# Sensors.net
KiCad netlist of a schematic drawn in Altium Designer
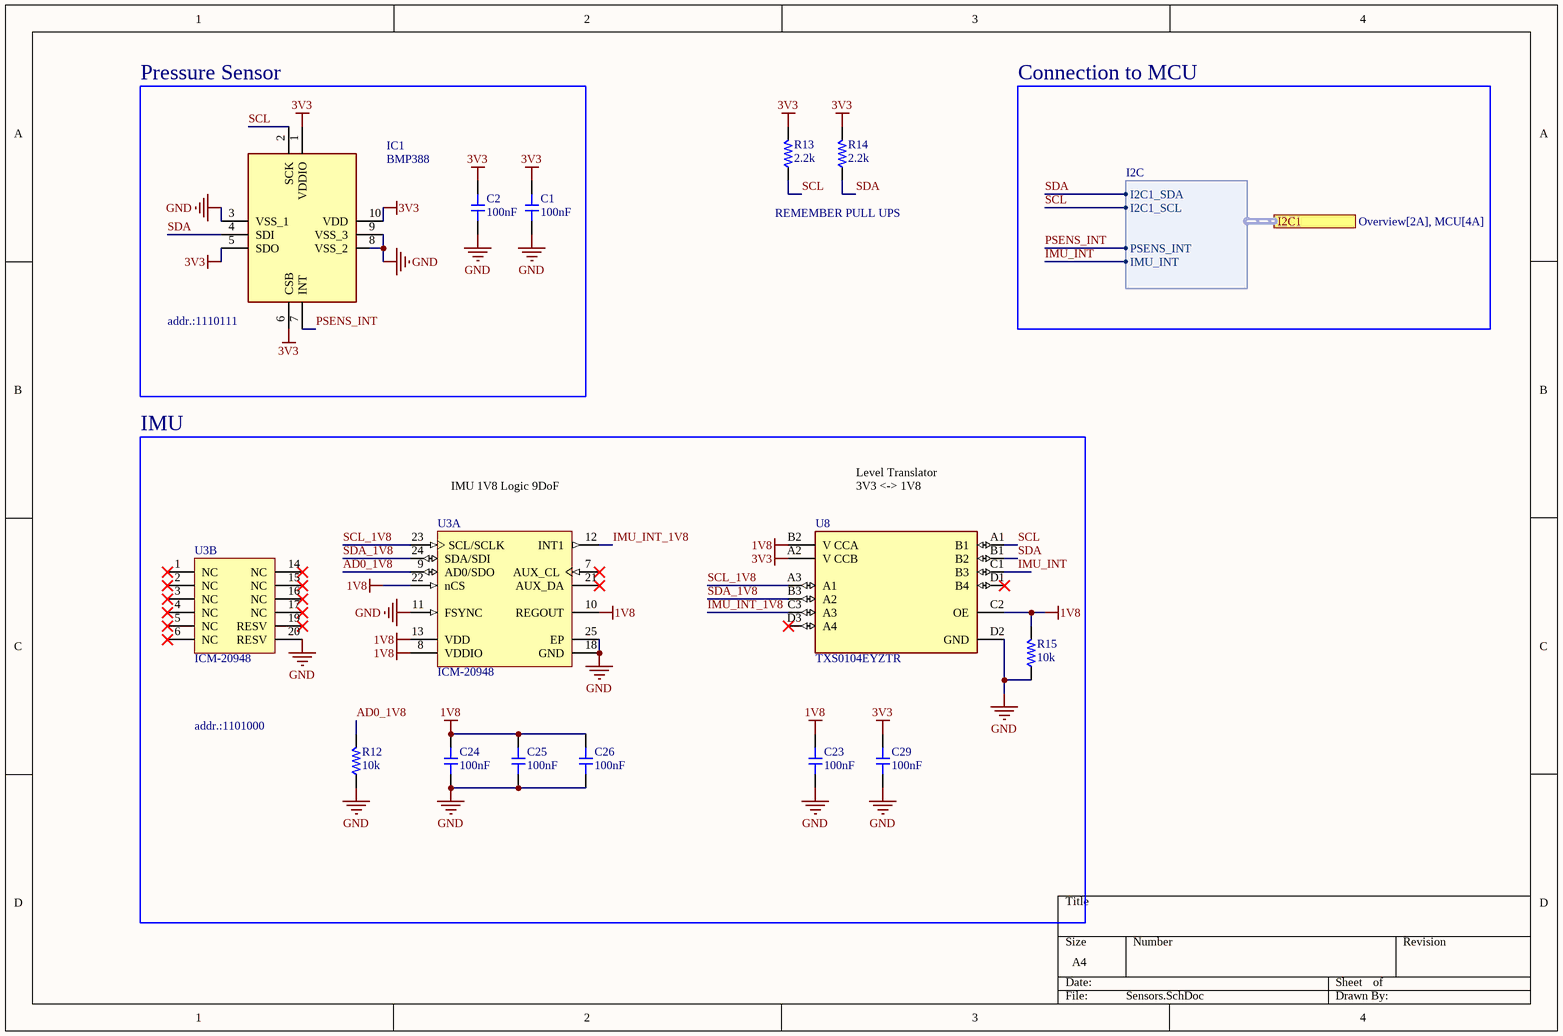
[diagram p0: Sensors.SchDoc]

(export (version "E")
  (design (tool "Eeschema 10.0.6"))
  (components
    (comp (ref "C1")
      (value "100nF")
      (footprint "CAP-0402")
      (description "Capacitor, Ceramic (MLCC), 100nF, ±10%, 16V, X7R, ±10%, SMD 0402")
      (fields (field (name "TOLERANCE") "10%") (field (name "JLCPCB BASIC PART") "Yes"))
      (libsource (lib "StrathSEDS") (part "GRM21BR61H106KE43L"))
    )
    (comp (ref "C2")
      (value "100nF")
      (footprint "CAP-0402")
      (description "Capacitor, Ceramic (MLCC), 100nF, ±10%, 16V, X7R, ±10%, SMD 0402")
      (fields (field (name "TOLERANCE") "10%") (field (name "JLCPCB BASIC PART") "Yes"))
      (libsource (lib "StrathSEDS") (part "GRM21BR61H106KE43L"))
    )
    (comp (ref "C23")
      (value "100nF")
      (footprint "CAP-0402")
      (description "Capacitor, Ceramic (MLCC), 100nF, ±10%, 16V, X7R, ±10%, SMD 0402")
      (fields (field (name "TOLERANCE") "10%") (field (name "JLCPCB BASIC PART") "Yes"))
      (libsource (lib "StrathSEDS") (part "GRM21BR61H106KE43L"))
    )
    (comp (ref "C24")
      (value "100nF")
      (footprint "CAP-0402")
      (description "Capacitor, Ceramic (MLCC), 100nF, ±10%, 16V, X7R, ±10%, SMD 0402")
      (fields (field (name "TOLERANCE") "10%") (field (name "JLCPCB BASIC PART") "Yes"))
      (libsource (lib "StrathSEDS") (part "GRM21BR61H106KE43L"))
    )
    (comp (ref "C25")
      (value "100nF")
      (footprint "CAP-0402")
      (description "Capacitor, Ceramic (MLCC), 100nF, ±10%, 16V, X7R, ±10%, SMD 0402")
      (fields (field (name "TOLERANCE") "10%") (field (name "JLCPCB BASIC PART") "Yes"))
      (libsource (lib "StrathSEDS") (part "GRM21BR61H106KE43L"))
    )
    (comp (ref "C26")
      (value "100nF")
      (footprint "CAP-0402")
      (description "Capacitor, Ceramic (MLCC), 100nF, ±10%, 16V, X7R, ±10%, SMD 0402")
      (fields (field (name "TOLERANCE") "10%") (field (name "JLCPCB BASIC PART") "Yes"))
      (libsource (lib "StrathSEDS") (part "GRM21BR61H106KE43L"))
    )
    (comp (ref "C29")
      (value "100nF")
      (footprint "CAP-0402")
      (description "Capacitor, Ceramic (MLCC), 100nF, ±10%, 16V, X7R, ±10%, SMD 0402")
      (fields (field (name "TOLERANCE") "10%") (field (name "JLCPCB BASIC PART") "Yes"))
      (libsource (lib "StrathSEDS") (part "GRM21BR61H106KE43L"))
    )
    (comp (ref "IC1")
      (value "BMP388")
      (footprint "BMP388")
      (description "Pressure Sensor 30kPa to 125kPa Absolute 10-Pin LGA")
      (fields (field (name "LCSC PART #") "C779278"))
      (libsource (lib "StrathSEDS") (part "BMP388"))
    )
    (comp (ref "R12")
      (value "10k")
      (footprint "RES-0402")
      (description "Resistor, 10kΩ, ±1%, 62.5mW, 50V, ±100ppm/℃, -55℃~+155℃, SMD 0402")
      (fields (field (name "TOLERANCE") "1%") (field (name "JLCPCB PART NUMBER") "C25744"))
      (libsource (lib "StrathSEDS") (part "1206W4F7500T5E"))
    )
    (comp (ref "R13")
      (value "2.2k")
      (footprint "RES-0402")
      (description "Resistor, 2.2kΩ, ±1%, 62.5mW, 50V, ±100ppm/℃, -55℃~+155℃, SMD 0402")
      (fields (field (name "JLCPCB BASIC PART") "Yes") (field (name "MANUFACTURER") "Uniroyal"))
      (libsource (lib "StrathSEDS") (part "1206W4F7500T5E"))
    )
    (comp (ref "R14")
      (value "2.2k")
      (footprint "RES-0402")
      (description "Resistor, 2.2kΩ, ±1%, 62.5mW, 50V, ±100ppm/℃, -55℃~+155℃, SMD 0402")
      (fields (field (name "JLCPCB BASIC PART") "Yes") (field (name "MANUFACTURER") "Uniroyal"))
      (libsource (lib "StrathSEDS") (part "1206W4F7500T5E"))
    )
    (comp (ref "R15")
      (value "10k")
      (footprint "RES-0402")
      (description "Resistor, 10kΩ, ±1%, 62.5mW, 50V, ±100ppm/℃, -55℃~+155℃, SMD 0402")
      (fields (field (name "TOLERANCE") "1%") (field (name "JLCPCB PART NUMBER") "C25744"))
      (libsource (lib "StrathSEDS") (part "1206W4F7500T5E"))
    )
    (comp (ref "U3")
      (value "ICM-20948")
      (footprint "TDK-QFN-24_L")
      (fields (field (name "JLCPCB PART NUMBER") "C726001"))
      (libsource (lib "StrathSEDS") (part "TDK-ICM-20948-QFN-24"))
    )
    (comp (ref "U8")
      (value "TXS0104EYZTR")
      (footprint "FP-YZT0012A-IPC_C")
      (description "Interface Circuit, PBGA12")
      (fields (field (name "JLCPCB PART NUMBER") "C478473"))
      (libsource (lib "StrathSEDS") (part "22a8ff7523e416a7c706a2509b4e62a"))
    )
  )
  (nets
    (net (code "2") (name "/AD0_1V8") (class "Default")
      (node (ref "R12") (pin "2") (pinfunction "2_2") (pintype "passive"))
      (node (ref "U3") (pin "9") (pinfunction "AD0/SDO_9") (pintype "bidirectional"))
    )
    (net (code "3") (name "/IMU_INT") (class "Default")
      (node (ref "U8") (pin "C1") (pinfunction "B3_C1") (pintype "bidirectional"))
    )
    (net (code "4") (name "/IMU_INT_1V8") (class "Default")
      (node (ref "U3") (pin "12") (pinfunction "INT1_12") (pintype "output"))
      (node (ref "U8") (pin "C3") (pinfunction "A3_C3") (pintype "bidirectional"))
    )
    (net (code "5") (name "/PSENS_INT") (class "Default")
      (node (ref "IC1") (pin "7") (pinfunction "INT_7") (pintype "passive"))
    )
    (net (code "6") (name "/SCL") (class "Default")
      (node (ref "IC1") (pin "2") (pinfunction "SCK_2") (pintype "passive"))
      (node (ref "R13") (pin "1") (pinfunction "1_1") (pintype "passive"))
      (node (ref "U8") (pin "A1") (pinfunction "B1_A1") (pintype "bidirectional"))
    )
    (net (code "7") (name "/SCL_1V8") (class "Default")
      (node (ref "U3") (pin "23") (pinfunction "SCL/SCLK_23") (pintype "input"))
      (node (ref "U8") (pin "A3") (pinfunction "A1_A3") (pintype "bidirectional"))
    )
    (net (code "8") (name "/SDA") (class "Default")
      (node (ref "IC1") (pin "4") (pinfunction "SDI_4") (pintype "passive"))
      (node (ref "R14") (pin "1") (pinfunction "1_1") (pintype "passive"))
      (node (ref "U8") (pin "B1") (pinfunction "B2_B1") (pintype "bidirectional"))
    )
    (net (code "9") (name "/SDA_1V8") (class "Default")
      (node (ref "U3") (pin "24") (pinfunction "SDA/SDI_24") (pintype "bidirectional"))
      (node (ref "U8") (pin "B3") (pinfunction "A2_B3") (pintype "bidirectional"))
    )
    (net (code "11") (name "1V8") (class "Default")
      (node (ref "C23") (pin "2") (pinfunction "2_2") (pintype "passive"))
      (node (ref "C24") (pin "2") (pinfunction "2_2") (pintype "passive"))
      (node (ref "C25") (pin "2") (pinfunction "2_2") (pintype "passive"))
      (node (ref "C26") (pin "2") (pinfunction "2_2") (pintype "passive"))
      (node (ref "R15") (pin "2") (pinfunction "2_2") (pintype "passive"))
      (node (ref "U3") (pin "10") (pinfunction "REGOUT_10") (pintype "passive"))
      (node (ref "U3") (pin "13") (pinfunction "VDD_13") (pintype "power_in"))
      (node (ref "U3") (pin "22") (pinfunction "nCS_22") (pintype "input"))
      (node (ref "U3") (pin "8") (pinfunction "VDDIO_8") (pintype "power_in"))
      (node (ref "U8") (pin "B2") (pinfunction "V_CCA_B2") (pintype "power_in"))
      (node (ref "U8") (pin "C2") (pinfunction "OE_C2") (pintype "passive"))
    )
    (net (code "12") (name "3V3") (class "Default")
      (node (ref "C1") (pin "2") (pinfunction "2_2") (pintype "passive"))
      (node (ref "C2") (pin "2") (pinfunction "2_2") (pintype "passive"))
      (node (ref "C29") (pin "2") (pinfunction "2_2") (pintype "passive"))
      (node (ref "IC1") (pin "1") (pinfunction "VDDIO_1") (pintype "passive"))
      (node (ref "IC1") (pin "10") (pinfunction "VDD_10") (pintype "passive"))
      (node (ref "IC1") (pin "5") (pinfunction "SDO_5") (pintype "passive"))
      (node (ref "IC1") (pin "6") (pinfunction "CSB_6") (pintype "passive"))
      (node (ref "R13") (pin "2") (pinfunction "2_2") (pintype "passive"))
      (node (ref "R14") (pin "2") (pinfunction "2_2") (pintype "passive"))
      (node (ref "U8") (pin "A2") (pinfunction "V_CCB_A2") (pintype "power_in"))
    )
    (net (code "13") (name "GND") (class "Default")
      (node (ref "C1") (pin "1") (pinfunction "1_1") (pintype "passive"))
      (node (ref "C2") (pin "1") (pinfunction "1_1") (pintype "passive"))
      (node (ref "C23") (pin "1") (pinfunction "1_1") (pintype "passive"))
      (node (ref "C24") (pin "1") (pinfunction "1_1") (pintype "passive"))
      (node (ref "C25") (pin "1") (pinfunction "1_1") (pintype "passive"))
      (node (ref "C26") (pin "1") (pinfunction "1_1") (pintype "passive"))
      (node (ref "C29") (pin "1") (pinfunction "1_1") (pintype "passive"))
      (node (ref "IC1") (pin "3") (pinfunction "VSS_1_3") (pintype "passive"))
      (node (ref "IC1") (pin "8") (pinfunction "VSS_2_8") (pintype "passive"))
      (node (ref "IC1") (pin "9") (pinfunction "VSS_3_9") (pintype "passive"))
      (node (ref "R12") (pin "1") (pinfunction "1_1") (pintype "passive"))
      (node (ref "R15") (pin "1") (pinfunction "1_1") (pintype "passive"))
      (node (ref "U3") (pin "11") (pinfunction "FSYNC_11") (pintype "input"))
      (node (ref "U3") (pin "18") (pinfunction "GND_18") (pintype "power_in"))
      (node (ref "U3") (pin "20") (pinfunction "RESV_20") (pintype "passive"))
      (node (ref "U3") (pin "25") (pinfunction "EP_25") (pintype "passive"))
      (node (ref "U8") (pin "D2") (pinfunction "GND_D2") (pintype "power_in"))
    )
    (net (code "14") (name "unconnected-(U3A-AUX_CL-Pad7)") (class "Default")
      (node (ref "U3") (pin "7") (pinfunction "AUX_CL_7") (pintype "input+no_connect"))
    )
    (net (code "15") (name "unconnected-(U3A-AUX_DA-Pad21)") (class "Default")
      (node (ref "U3") (pin "21") (pinfunction "AUX_DA_21") (pintype "passive+no_connect"))
    )
    (net (code "16") (name "unconnected-(U3B-NC-Pad1)") (class "Default")
      (node (ref "U3") (pin "1") (pinfunction "NC_1") (pintype "passive+no_connect"))
    )
    (net (code "17") (name "unconnected-(U3B-NC-Pad2)") (class "Default")
      (node (ref "U3") (pin "2") (pinfunction "NC_2") (pintype "passive+no_connect"))
    )
    (net (code "18") (name "unconnected-(U3B-NC-Pad3)") (class "Default")
      (node (ref "U3") (pin "3") (pinfunction "NC_3") (pintype "passive+no_connect"))
    )
    (net (code "19") (name "unconnected-(U3B-NC-Pad4)") (class "Default")
      (node (ref "U3") (pin "4") (pinfunction "NC_4") (pintype "passive+no_connect"))
    )
    (net (code "20") (name "unconnected-(U3B-NC-Pad5)") (class "Default")
      (node (ref "U3") (pin "5") (pinfunction "NC_5") (pintype "passive+no_connect"))
    )
    (net (code "21") (name "unconnected-(U3B-NC-Pad6)") (class "Default")
      (node (ref "U3") (pin "6") (pinfunction "NC_6") (pintype "passive+no_connect"))
    )
    (net (code "22") (name "unconnected-(U3B-NC-Pad14)") (class "Default")
      (node (ref "U3") (pin "14") (pinfunction "NC_14") (pintype "passive+no_connect"))
    )
    (net (code "23") (name "unconnected-(U3B-NC-Pad15)") (class "Default")
      (node (ref "U3") (pin "15") (pinfunction "NC_15") (pintype "passive+no_connect"))
    )
    (net (code "24") (name "unconnected-(U3B-NC-Pad16)") (class "Default")
      (node (ref "U3") (pin "16") (pinfunction "NC_16") (pintype "passive+no_connect"))
    )
    (net (code "25") (name "unconnected-(U3B-NC-Pad17)") (class "Default")
      (node (ref "U3") (pin "17") (pinfunction "NC_17") (pintype "passive+no_connect"))
    )
    (net (code "26") (name "unconnected-(U3B-RESV-Pad19)") (class "Default")
      (node (ref "U3") (pin "19") (pinfunction "RESV_19") (pintype "passive+no_connect"))
    )
    (net (code "27") (name "unconnected-(U8-A4-PadD3)") (class "Default")
      (node (ref "U8") (pin "D3") (pinfunction "A4_D3") (pintype "bidirectional+no_connect"))
    )
    (net (code "28") (name "unconnected-(U8-B4-PadD1)") (class "Default")
      (node (ref "U8") (pin "D1") (pinfunction "B4_D1") (pintype "bidirectional+no_connect"))
    )
  )
)
